# receiver.net
KiCad netlist of a schematic drawn in EAGLE
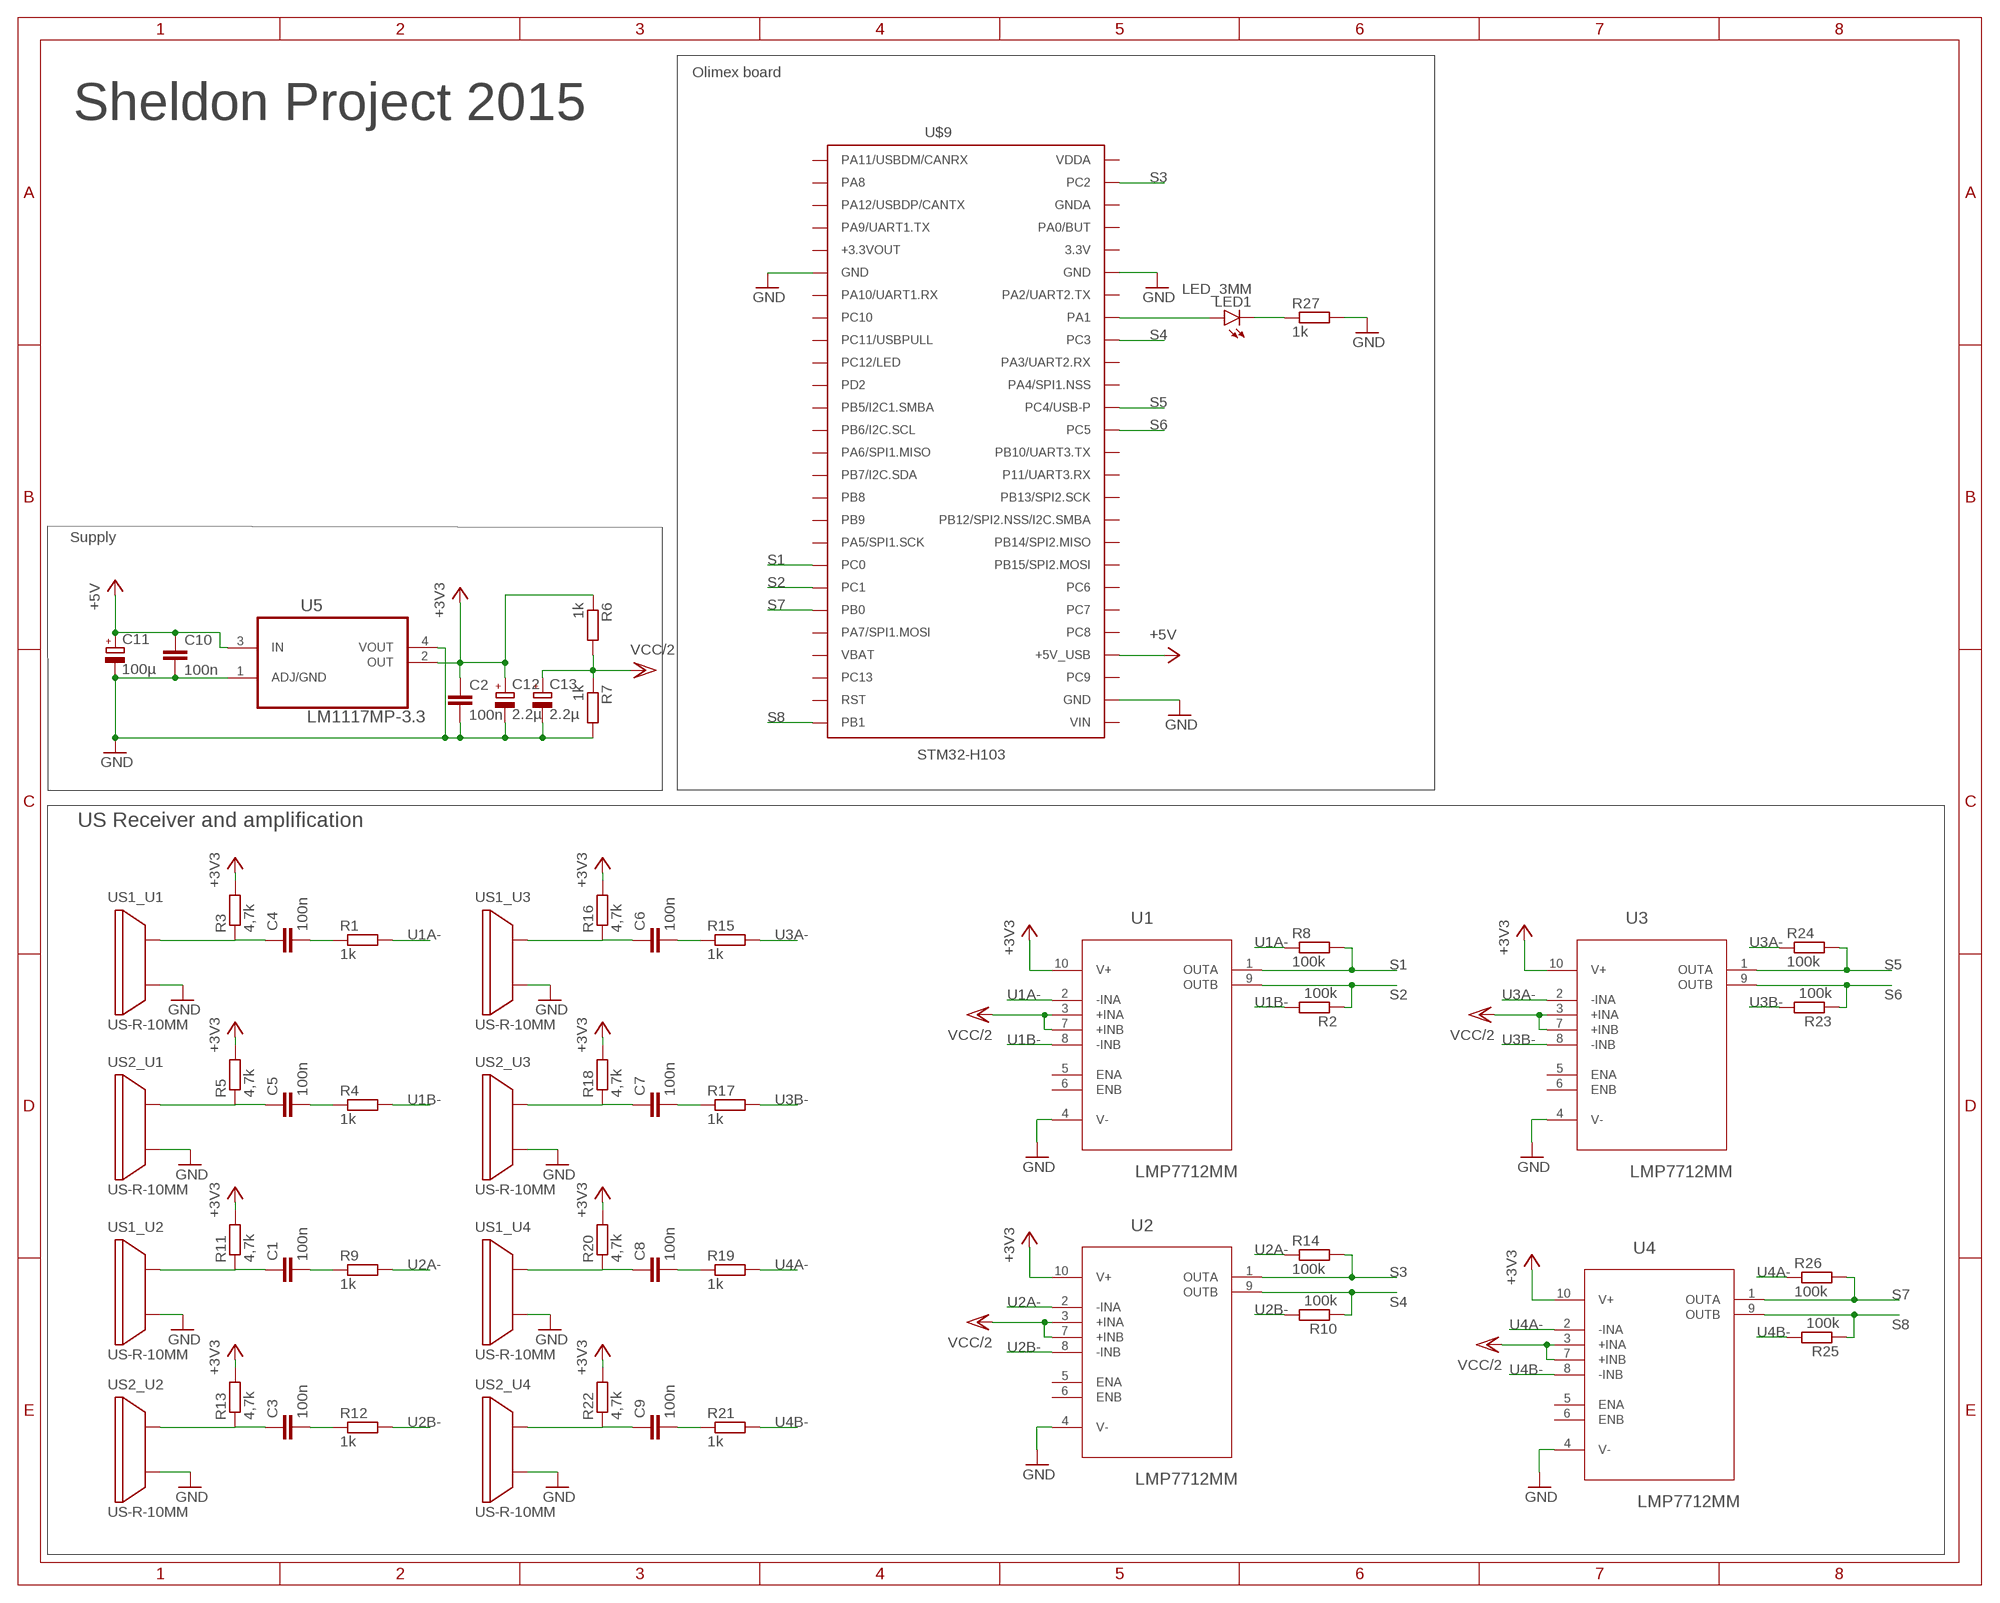
[diagram p0: schematic, sheet 1]

(export (version "E")
  (design (tool "Eeschema 10.0.6"))
  (components
    (comp (ref "C1")
      (value "100n")
      (footprint "eagle-import:C0603")
      (libsource (lib "eagle-import") (part "C-EUC0603"))
    )
    (comp (ref "C2")
      (value "100n")
      (footprint "eagle-import:C0603")
      (libsource (lib "eagle-import") (part "C-EUC0603"))
    )
    (comp (ref "C3")
      (value "100n")
      (footprint "eagle-import:C0603")
      (libsource (lib "eagle-import") (part "C-EUC0603"))
    )
    (comp (ref "C4")
      (value "100n")
      (footprint "eagle-import:C0603")
      (libsource (lib "eagle-import") (part "C-EUC0603"))
    )
    (comp (ref "C5")
      (value "100n")
      (footprint "eagle-import:C0603")
      (libsource (lib "eagle-import") (part "C-EUC0603"))
    )
    (comp (ref "C6")
      (value "100n")
      (footprint "eagle-import:C0603")
      (libsource (lib "eagle-import") (part "C-EUC0603"))
    )
    (comp (ref "C7")
      (value "100n")
      (footprint "eagle-import:C0603")
      (libsource (lib "eagle-import") (part "C-EUC0603"))
    )
    (comp (ref "C8")
      (value "100n")
      (footprint "eagle-import:C0603")
      (libsource (lib "eagle-import") (part "C-EUC0603"))
    )
    (comp (ref "C9")
      (value "100n")
      (footprint "eagle-import:C0603")
      (libsource (lib "eagle-import") (part "C-EUC0603"))
    )
    (comp (ref "C10")
      (value "100n")
      (footprint "eagle-import:C0603")
      (libsource (lib "eagle-import") (part "C-EUC0603"))
    )
    (comp (ref "C11")
      (value "100µ")
      (footprint "eagle-import:E2,5-6")
      (libsource (lib "eagle-import") (part "CPOL_DIAM5MM"))
    )
    (comp (ref "C12")
      (value "2.2µ")
      (footprint "eagle-import:E2,5-6")
      (libsource (lib "eagle-import") (part "CPOL_DIAM5MM"))
    )
    (comp (ref "C13")
      (value "2.2µ")
      (footprint "eagle-import:E2,5-6")
      (libsource (lib "eagle-import") (part "CPOL_DIAM5MM"))
    )
    (comp (ref "LED1")
      (value "LED_3MM")
      (footprint "eagle-import:LED3MM")
      (libsource (lib "eagle-import") (part "LED_3MM"))
    )
    (comp (ref "R1")
      (value "1k")
      (footprint "eagle-import:R0603")
      (libsource (lib "eagle-import") (part "R-EU_R0603"))
    )
    (comp (ref "R2")
      (value "100k")
      (footprint "eagle-import:R0603")
      (libsource (lib "eagle-import") (part "R-EU_R0603"))
    )
    (comp (ref "R3")
      (value "4,7k")
      (footprint "eagle-import:R0603")
      (libsource (lib "eagle-import") (part "R-EU_R0603"))
    )
    (comp (ref "R4")
      (value "1k")
      (footprint "eagle-import:R0603")
      (libsource (lib "eagle-import") (part "R-EU_R0603"))
    )
    (comp (ref "R5")
      (value "4,7k")
      (footprint "eagle-import:R0603")
      (libsource (lib "eagle-import") (part "R-EU_R0603"))
    )
    (comp (ref "R6")
      (value "1k")
      (footprint "eagle-import:R0603")
      (libsource (lib "eagle-import") (part "R-EU_R0603"))
    )
    (comp (ref "R7")
      (value "1k")
      (footprint "eagle-import:R0603")
      (libsource (lib "eagle-import") (part "R-EU_R0603"))
    )
    (comp (ref "R8")
      (value "100k")
      (footprint "eagle-import:R0603")
      (libsource (lib "eagle-import") (part "R-EU_R0603"))
    )
    (comp (ref "R9")
      (value "1k")
      (footprint "eagle-import:R0603")
      (libsource (lib "eagle-import") (part "R-EU_R0603"))
    )
    (comp (ref "R10")
      (value "100k")
      (footprint "eagle-import:R0603")
      (libsource (lib "eagle-import") (part "R-EU_R0603"))
    )
    (comp (ref "R11")
      (value "4,7k")
      (footprint "eagle-import:R0603")
      (libsource (lib "eagle-import") (part "R-EU_R0603"))
    )
    (comp (ref "R12")
      (value "1k")
      (footprint "eagle-import:R0603")
      (libsource (lib "eagle-import") (part "R-EU_R0603"))
    )
    (comp (ref "R13")
      (value "4,7k")
      (footprint "eagle-import:R0603")
      (libsource (lib "eagle-import") (part "R-EU_R0603"))
    )
    (comp (ref "R14")
      (value "100k")
      (footprint "eagle-import:R0603")
      (libsource (lib "eagle-import") (part "R-EU_R0603"))
    )
    (comp (ref "R15")
      (value "1k")
      (footprint "eagle-import:R0603")
      (libsource (lib "eagle-import") (part "R-EU_R0603"))
    )
    (comp (ref "R16")
      (value "4,7k")
      (footprint "eagle-import:R0603")
      (libsource (lib "eagle-import") (part "R-EU_R0603"))
    )
    (comp (ref "R17")
      (value "1k")
      (footprint "eagle-import:R0603")
      (libsource (lib "eagle-import") (part "R-EU_R0603"))
    )
    (comp (ref "R18")
      (value "4,7k")
      (footprint "eagle-import:R0603")
      (libsource (lib "eagle-import") (part "R-EU_R0603"))
    )
    (comp (ref "R19")
      (value "1k")
      (footprint "eagle-import:R0603")
      (libsource (lib "eagle-import") (part "R-EU_R0603"))
    )
    (comp (ref "R20")
      (value "4,7k")
      (footprint "eagle-import:R0603")
      (libsource (lib "eagle-import") (part "R-EU_R0603"))
    )
    (comp (ref "R21")
      (value "1k")
      (footprint "eagle-import:R0603")
      (libsource (lib "eagle-import") (part "R-EU_R0603"))
    )
    (comp (ref "R22")
      (value "4,7k")
      (footprint "eagle-import:R0603")
      (libsource (lib "eagle-import") (part "R-EU_R0603"))
    )
    (comp (ref "R23")
      (value "100k")
      (footprint "eagle-import:R0603")
      (libsource (lib "eagle-import") (part "R-EU_R0603"))
    )
    (comp (ref "R24")
      (value "100k")
      (footprint "eagle-import:R0603")
      (libsource (lib "eagle-import") (part "R-EU_R0603"))
    )
    (comp (ref "R25")
      (value "100k")
      (footprint "eagle-import:R0603")
      (libsource (lib "eagle-import") (part "R-EU_R0603"))
    )
    (comp (ref "R26")
      (value "100k")
      (footprint "eagle-import:R0603")
      (libsource (lib "eagle-import") (part "R-EU_R0603"))
    )
    (comp (ref "R27")
      (value "1k")
      (footprint "eagle-import:R0603")
      (libsource (lib "eagle-import") (part "R-EU_R0603"))
    )
    (comp (ref "U$9")
      (value "STM32-H103")
      (footprint "eagle-import:STM32-H103")
      (libsource (lib "eagle-import") (part "STM32-H103"))
    )
    (comp (ref "U1")
      (value "LMP7712MM")
      (footprint "eagle-import:SOP50P490X110-10N")
      (libsource (lib "eagle-import") (part "LMP7712MM"))
    )
    (comp (ref "U2")
      (value "LMP7712MM")
      (footprint "eagle-import:SOP50P490X110-10N")
      (libsource (lib "eagle-import") (part "LMP7712MM"))
    )
    (comp (ref "U3")
      (value "LMP7712MM")
      (footprint "eagle-import:SOP50P490X110-10N")
      (libsource (lib "eagle-import") (part "LMP7712MM"))
    )
    (comp (ref "U4")
      (value "LMP7712MM")
      (footprint "eagle-import:SOP50P490X110-10N")
      (libsource (lib "eagle-import") (part "LMP7712MM"))
    )
    (comp (ref "U5")
      (value "LM1117MP-3.3")
      (footprint "eagle-import:SOT230P696X180-4N")
      (libsource (lib "eagle-import") (part "LM1117MP-3.3"))
    )
    (comp (ref "US1_U1")
      (value "US-R-10MM")
      (footprint "eagle-import:US-R-10MM")
      (libsource (lib "eagle-import") (part "US-R-10MM"))
    )
    (comp (ref "US1_U2")
      (value "US-R-10MM")
      (footprint "eagle-import:US-R-10MM")
      (libsource (lib "eagle-import") (part "US-R-10MM"))
    )
    (comp (ref "US1_U3")
      (value "US-R-10MM")
      (footprint "eagle-import:US-R-10MM")
      (libsource (lib "eagle-import") (part "US-R-10MM"))
    )
    (comp (ref "US1_U4")
      (value "US-R-10MM")
      (footprint "eagle-import:US-R-10MM")
      (libsource (lib "eagle-import") (part "US-R-10MM"))
    )
    (comp (ref "US2_U1")
      (value "US-R-10MM")
      (footprint "eagle-import:US-R-10MM")
      (libsource (lib "eagle-import") (part "US-R-10MM"))
    )
    (comp (ref "US2_U2")
      (value "US-R-10MM")
      (footprint "eagle-import:US-R-10MM")
      (libsource (lib "eagle-import") (part "US-R-10MM"))
    )
    (comp (ref "US2_U3")
      (value "US-R-10MM")
      (footprint "eagle-import:US-R-10MM")
      (libsource (lib "eagle-import") (part "US-R-10MM"))
    )
    (comp (ref "US2_U4")
      (value "US-R-10MM")
      (footprint "eagle-import:US-R-10MM")
      (libsource (lib "eagle-import") (part "US-R-10MM"))
    )
  )
  (nets
    (net (code "1") (name "+3V3") (class "Default")
      (node (ref "C12") (pin "+") (pinfunction "P$1_+") (pintype "passive"))
      (node (ref "C2") (pin "1") (pinfunction "1_1") (pintype "passive"))
      (node (ref "R11") (pin "2") (pinfunction "2_2") (pintype "passive"))
      (node (ref "R13") (pin "2") (pinfunction "2_2") (pintype "passive"))
      (node (ref "R16") (pin "2") (pinfunction "2_2") (pintype "passive"))
      (node (ref "R18") (pin "2") (pinfunction "2_2") (pintype "passive"))
      (node (ref "R20") (pin "2") (pinfunction "2_2") (pintype "passive"))
      (node (ref "R22") (pin "2") (pinfunction "2_2") (pintype "passive"))
      (node (ref "R3") (pin "2") (pinfunction "2_2") (pintype "passive"))
      (node (ref "R5") (pin "2") (pinfunction "2_2") (pintype "passive"))
      (node (ref "R6") (pin "1") (pinfunction "1_1") (pintype "passive"))
      (node (ref "U1") (pin "10") (pinfunction "V+_10") (pintype "power_in"))
      (node (ref "U2") (pin "10") (pinfunction "V+_10") (pintype "power_in"))
      (node (ref "U3") (pin "10") (pinfunction "V+_10") (pintype "power_in"))
      (node (ref "U4") (pin "10") (pinfunction "V+_10") (pintype "power_in"))
      (node (ref "U5") (pin "2") (pinfunction "OUT_2") (pintype "output"))
    )
    (net (code "2") (name "+5V") (class "Default")
      (node (ref "C10") (pin "1") (pinfunction "1_1") (pintype "passive"))
      (node (ref "C11") (pin "+") (pinfunction "P$1_+") (pintype "passive"))
      (node (ref "U$9") (pin "+5V_USB") (pinfunction "+5V_USB_+5V_USB") (pintype "bidirectional"))
      (node (ref "U5") (pin "3") (pinfunction "IN_3") (pintype "input"))
    )
    (net (code "3") (name "/S1") (class "Default")
      (node (ref "R8") (pin "2") (pinfunction "2_2") (pintype "passive"))
      (node (ref "U$9") (pin "PC0") (pinfunction "PC0_PC0") (pintype "bidirectional"))
      (node (ref "U1") (pin "1") (pinfunction "OUTA_1") (pintype "output"))
    )
    (net (code "4") (name "/S2") (class "Default")
      (node (ref "R2") (pin "1") (pinfunction "1_1") (pintype "passive"))
      (node (ref "U$9") (pin "PC1") (pinfunction "PC1_PC1") (pintype "bidirectional"))
      (node (ref "U1") (pin "9") (pinfunction "OUTB_9") (pintype "output"))
    )
    (net (code "5") (name "/S3") (class "Default")
      (node (ref "R14") (pin "2") (pinfunction "2_2") (pintype "passive"))
      (node (ref "U$9") (pin "PC2") (pinfunction "PC2_PC2") (pintype "bidirectional"))
      (node (ref "U2") (pin "1") (pinfunction "OUTA_1") (pintype "output"))
    )
    (net (code "6") (name "/S4") (class "Default")
      (node (ref "R10") (pin "1") (pinfunction "1_1") (pintype "passive"))
      (node (ref "U$9") (pin "PC3") (pinfunction "PC3_PC3") (pintype "bidirectional"))
      (node (ref "U2") (pin "9") (pinfunction "OUTB_9") (pintype "output"))
    )
    (net (code "7") (name "/S5") (class "Default")
      (node (ref "R24") (pin "2") (pinfunction "2_2") (pintype "passive"))
      (node (ref "U$9") (pin "PC4/USB-P") (pinfunction "PC4/USB-P_PC4/USB-P") (pintype "bidirectional"))
      (node (ref "U3") (pin "1") (pinfunction "OUTA_1") (pintype "output"))
    )
    (net (code "8") (name "/S6") (class "Default")
      (node (ref "R23") (pin "1") (pinfunction "1_1") (pintype "passive"))
      (node (ref "U$9") (pin "PC5") (pinfunction "PC5_PC5") (pintype "bidirectional"))
      (node (ref "U3") (pin "9") (pinfunction "OUTB_9") (pintype "output"))
    )
    (net (code "9") (name "/S7") (class "Default")
      (node (ref "R26") (pin "2") (pinfunction "2_2") (pintype "passive"))
      (node (ref "U$9") (pin "PB0") (pinfunction "PB0_PB0") (pintype "bidirectional"))
      (node (ref "U4") (pin "1") (pinfunction "OUTA_1") (pintype "output"))
    )
    (net (code "10") (name "/S8") (class "Default")
      (node (ref "R25") (pin "1") (pinfunction "1_1") (pintype "passive"))
      (node (ref "U$9") (pin "PB1") (pinfunction "PB1_PB1") (pintype "bidirectional"))
      (node (ref "U4") (pin "9") (pinfunction "OUTB_9") (pintype "output"))
    )
    (net (code "11") (name "/U1A-") (class "Default")
      (node (ref "R1") (pin "2") (pinfunction "2_2") (pintype "passive"))
      (node (ref "R8") (pin "1") (pinfunction "1_1") (pintype "passive"))
      (node (ref "U1") (pin "2") (pinfunction "-INA_2") (pintype "input"))
    )
    (net (code "12") (name "/U1B-") (class "Default")
      (node (ref "R2") (pin "2") (pinfunction "2_2") (pintype "passive"))
      (node (ref "R4") (pin "2") (pinfunction "2_2") (pintype "passive"))
      (node (ref "U1") (pin "8") (pinfunction "-INB_8") (pintype "input"))
    )
    (net (code "13") (name "/U2A-") (class "Default")
      (node (ref "R14") (pin "1") (pinfunction "1_1") (pintype "passive"))
      (node (ref "R9") (pin "2") (pinfunction "2_2") (pintype "passive"))
      (node (ref "U2") (pin "2") (pinfunction "-INA_2") (pintype "input"))
    )
    (net (code "14") (name "/U2B-") (class "Default")
      (node (ref "R10") (pin "2") (pinfunction "2_2") (pintype "passive"))
      (node (ref "R12") (pin "2") (pinfunction "2_2") (pintype "passive"))
      (node (ref "U2") (pin "8") (pinfunction "-INB_8") (pintype "input"))
    )
    (net (code "15") (name "/U3A-") (class "Default")
      (node (ref "R15") (pin "2") (pinfunction "2_2") (pintype "passive"))
      (node (ref "R24") (pin "1") (pinfunction "1_1") (pintype "passive"))
      (node (ref "U3") (pin "2") (pinfunction "-INA_2") (pintype "input"))
    )
    (net (code "16") (name "/U3B-") (class "Default")
      (node (ref "R17") (pin "2") (pinfunction "2_2") (pintype "passive"))
      (node (ref "R23") (pin "2") (pinfunction "2_2") (pintype "passive"))
      (node (ref "U3") (pin "8") (pinfunction "-INB_8") (pintype "input"))
    )
    (net (code "17") (name "/U4A-") (class "Default")
      (node (ref "R19") (pin "2") (pinfunction "2_2") (pintype "passive"))
      (node (ref "R26") (pin "1") (pinfunction "1_1") (pintype "passive"))
      (node (ref "U4") (pin "2") (pinfunction "-INA_2") (pintype "input"))
    )
    (net (code "18") (name "/U4B-") (class "Default")
      (node (ref "R21") (pin "2") (pinfunction "2_2") (pintype "passive"))
      (node (ref "R25") (pin "2") (pinfunction "2_2") (pintype "passive"))
      (node (ref "U4") (pin "8") (pinfunction "-INB_8") (pintype "input"))
    )
    (net (code "19") (name "GND") (class "Default")
      (node (ref "C10") (pin "2") (pinfunction "2_2") (pintype "passive"))
      (node (ref "C11") (pin "-") (pinfunction "P$2_-") (pintype "passive"))
      (node (ref "C12") (pin "-") (pinfunction "P$2_-") (pintype "passive"))
      (node (ref "C13") (pin "-") (pinfunction "P$2_-") (pintype "passive"))
      (node (ref "C2") (pin "2") (pinfunction "2_2") (pintype "passive"))
      (node (ref "R27") (pin "2") (pinfunction "2_2") (pintype "passive"))
      (node (ref "R7") (pin "2") (pinfunction "2_2") (pintype "passive"))
      (node (ref "U$9") (pin "GND@1") (pinfunction "GND_GND@1") (pintype "bidirectional"))
      (node (ref "U$9") (pin "GND@2") (pinfunction "GND_GND@2") (pintype "bidirectional"))
      (node (ref "U$9") (pin "GND@3") (pinfunction "GND_GND@3") (pintype "bidirectional"))
      (node (ref "U1") (pin "4") (pinfunction "V-_4") (pintype "power_in"))
      (node (ref "U2") (pin "4") (pinfunction "V-_4") (pintype "power_in"))
      (node (ref "U3") (pin "4") (pinfunction "V-_4") (pintype "power_in"))
      (node (ref "U4") (pin "4") (pinfunction "V-_4") (pintype "power_in"))
      (node (ref "U5") (pin "1") (pinfunction "ADJ/GND_1") (pintype "passive"))
      (node (ref "U5") (pin "4") (pinfunction "VOUT_4") (pintype "output"))
      (node (ref "US1_U1") (pin "P$2") (pinfunction "P$2_P$2") (pintype "output"))
      (node (ref "US1_U2") (pin "P$2") (pinfunction "P$2_P$2") (pintype "output"))
      (node (ref "US1_U3") (pin "P$2") (pinfunction "P$2_P$2") (pintype "output"))
      (node (ref "US1_U4") (pin "P$2") (pinfunction "P$2_P$2") (pintype "output"))
      (node (ref "US2_U1") (pin "P$2") (pinfunction "P$2_P$2") (pintype "output"))
      (node (ref "US2_U2") (pin "P$2") (pinfunction "P$2_P$2") (pintype "output"))
      (node (ref "US2_U3") (pin "P$2") (pinfunction "P$2_P$2") (pintype "output"))
      (node (ref "US2_U4") (pin "P$2") (pinfunction "P$2_P$2") (pintype "output"))
    )
    (net (code "20") (name "Net-(C1-Pad1)") (class "Default")
      (node (ref "C1") (pin "1") (pinfunction "1_1") (pintype "passive"))
      (node (ref "R11") (pin "1") (pinfunction "1_1") (pintype "passive"))
      (node (ref "US1_U2") (pin "P$1") (pinfunction "P$1_P$1") (pintype "output"))
    )
    (net (code "21") (name "Net-(C1-Pad2)") (class "Default")
      (node (ref "C1") (pin "2") (pinfunction "2_2") (pintype "passive"))
      (node (ref "R9") (pin "1") (pinfunction "1_1") (pintype "passive"))
    )
    (net (code "22") (name "Net-(C3-Pad1)") (class "Default")
      (node (ref "C3") (pin "1") (pinfunction "1_1") (pintype "passive"))
      (node (ref "R13") (pin "1") (pinfunction "1_1") (pintype "passive"))
      (node (ref "US2_U2") (pin "P$1") (pinfunction "P$1_P$1") (pintype "output"))
    )
    (net (code "23") (name "Net-(C3-Pad2)") (class "Default")
      (node (ref "C3") (pin "2") (pinfunction "2_2") (pintype "passive"))
      (node (ref "R12") (pin "1") (pinfunction "1_1") (pintype "passive"))
    )
    (net (code "24") (name "Net-(C4-Pad1)") (class "Default")
      (node (ref "C4") (pin "1") (pinfunction "1_1") (pintype "passive"))
      (node (ref "R3") (pin "1") (pinfunction "1_1") (pintype "passive"))
      (node (ref "US1_U1") (pin "P$1") (pinfunction "P$1_P$1") (pintype "output"))
    )
    (net (code "25") (name "Net-(C4-Pad2)") (class "Default")
      (node (ref "C4") (pin "2") (pinfunction "2_2") (pintype "passive"))
      (node (ref "R1") (pin "1") (pinfunction "1_1") (pintype "passive"))
    )
    (net (code "26") (name "Net-(C5-Pad1)") (class "Default")
      (node (ref "C5") (pin "1") (pinfunction "1_1") (pintype "passive"))
      (node (ref "R5") (pin "1") (pinfunction "1_1") (pintype "passive"))
      (node (ref "US2_U1") (pin "P$1") (pinfunction "P$1_P$1") (pintype "output"))
    )
    (net (code "27") (name "Net-(C5-Pad2)") (class "Default")
      (node (ref "C5") (pin "2") (pinfunction "2_2") (pintype "passive"))
      (node (ref "R4") (pin "1") (pinfunction "1_1") (pintype "passive"))
    )
    (net (code "28") (name "Net-(C6-Pad1)") (class "Default")
      (node (ref "C6") (pin "1") (pinfunction "1_1") (pintype "passive"))
      (node (ref "R16") (pin "1") (pinfunction "1_1") (pintype "passive"))
      (node (ref "US1_U3") (pin "P$1") (pinfunction "P$1_P$1") (pintype "output"))
    )
    (net (code "29") (name "Net-(C6-Pad2)") (class "Default")
      (node (ref "C6") (pin "2") (pinfunction "2_2") (pintype "passive"))
      (node (ref "R15") (pin "1") (pinfunction "1_1") (pintype "passive"))
    )
    (net (code "30") (name "Net-(C7-Pad1)") (class "Default")
      (node (ref "C7") (pin "1") (pinfunction "1_1") (pintype "passive"))
      (node (ref "R18") (pin "1") (pinfunction "1_1") (pintype "passive"))
      (node (ref "US2_U3") (pin "P$1") (pinfunction "P$1_P$1") (pintype "output"))
    )
    (net (code "31") (name "Net-(C7-Pad2)") (class "Default")
      (node (ref "C7") (pin "2") (pinfunction "2_2") (pintype "passive"))
      (node (ref "R17") (pin "1") (pinfunction "1_1") (pintype "passive"))
    )
    (net (code "32") (name "Net-(C8-Pad1)") (class "Default")
      (node (ref "C8") (pin "1") (pinfunction "1_1") (pintype "passive"))
      (node (ref "R20") (pin "1") (pinfunction "1_1") (pintype "passive"))
      (node (ref "US1_U4") (pin "P$1") (pinfunction "P$1_P$1") (pintype "output"))
    )
    (net (code "33") (name "Net-(C8-Pad2)") (class "Default")
      (node (ref "C8") (pin "2") (pinfunction "2_2") (pintype "passive"))
      (node (ref "R19") (pin "1") (pinfunction "1_1") (pintype "passive"))
    )
    (net (code "34") (name "Net-(C9-Pad1)") (class "Default")
      (node (ref "C9") (pin "1") (pinfunction "1_1") (pintype "passive"))
      (node (ref "R22") (pin "1") (pinfunction "1_1") (pintype "passive"))
      (node (ref "US2_U4") (pin "P$1") (pinfunction "P$1_P$1") (pintype "output"))
    )
    (net (code "35") (name "Net-(C9-Pad2)") (class "Default")
      (node (ref "C9") (pin "2") (pinfunction "2_2") (pintype "passive"))
      (node (ref "R21") (pin "1") (pinfunction "1_1") (pintype "passive"))
    )
    (net (code "36") (name "Net-(LED1-C)") (class "Default")
      (node (ref "LED1") (pin "K") (pinfunction "C_K") (pintype "passive"))
      (node (ref "R27") (pin "1") (pinfunction "1_1") (pintype "passive"))
    )
    (net (code "37") (name "Net-(LED1-PadA)") (class "Default")
      (node (ref "LED1") (pin "A") (pinfunction "A_A") (pintype "passive"))
      (node (ref "U$9") (pin "PA1") (pinfunction "PA1_PA1") (pintype "bidirectional"))
    )
    (net (code "38") (name "VCC{slash}2") (class "Default")
      (node (ref "C13") (pin "+") (pinfunction "P$1_+") (pintype "passive"))
      (node (ref "R6") (pin "2") (pinfunction "2_2") (pintype "passive"))
      (node (ref "R7") (pin "1") (pinfunction "1_1") (pintype "passive"))
      (node (ref "U1") (pin "3") (pinfunction "+INA_3") (pintype "input"))
      (node (ref "U1") (pin "7") (pinfunction "+INB_7") (pintype "input"))
      (node (ref "U2") (pin "3") (pinfunction "+INA_3") (pintype "input"))
      (node (ref "U2") (pin "7") (pinfunction "+INB_7") (pintype "input"))
      (node (ref "U3") (pin "3") (pinfunction "+INA_3") (pintype "input"))
      (node (ref "U3") (pin "7") (pinfunction "+INB_7") (pintype "input"))
      (node (ref "U4") (pin "3") (pinfunction "+INA_3") (pintype "input"))
      (node (ref "U4") (pin "7") (pinfunction "+INB_7") (pintype "input"))
    )
    (net (code "39") (name "unconnected-(U$9-Pad+3.3VOUT)") (class "Default")
      (node (ref "U$9") (pin "+3.3VOUT") (pinfunction "+3.3VOUT_+3.3VOUT") (pintype "bidirectional"))
    )
    (net (code "40") (name "unconnected-(U$9-Pad3.3V)") (class "Default")
      (node (ref "U$9") (pin "3.3V") (pinfunction "3.3V_3.3V") (pintype "bidirectional"))
    )
    (net (code "41") (name "unconnected-(U$9-PadGNDA)") (class "Default")
      (node (ref "U$9") (pin "GNDA") (pinfunction "GNDA_GNDA") (pintype "bidirectional"))
    )
    (net (code "42") (name "unconnected-(U$9-PadP11{slash}UART3.RX)") (class "Default")
      (node (ref "U$9") (pin "P11/UART3.RX") (pinfunction "P11/UART3.RX_P11/UART3.RX") (pintype "bidirectional"))
    )
    (net (code "43") (name "unconnected-(U$9-PadPA0{slash}BUT)") (class "Default")
      (node (ref "U$9") (pin "PA0/BUT") (pinfunction "PA0/BUT_PA0/BUT") (pintype "bidirectional"))
    )
    (net (code "44") (name "unconnected-(U$9-PadPA2{slash}UART2.TX)") (class "Default")
      (node (ref "U$9") (pin "PA2/UART2.TX") (pinfunction "PA2/UART2.TX_PA2/UART2.TX") (pintype "bidirectional"))
    )
    (net (code "45") (name "unconnected-(U$9-PadPA3{slash}UART2.RX)") (class "Default")
      (node (ref "U$9") (pin "PA3/UART2.RX") (pinfunction "PA3/UART2.RX_PA3/UART2.RX") (pintype "bidirectional"))
    )
    (net (code "46") (name "unconnected-(U$9-PadPA4{slash}SPI1.NSS)") (class "Default")
      (node (ref "U$9") (pin "PA4/SPI1.NSS") (pinfunction "PA4/SPI1.NSS_PA4/SPI1.NSS") (pintype "bidirectional"))
    )
    (net (code "47") (name "unconnected-(U$9-PadPA5{slash}SPI1.SCK)") (class "Default")
      (node (ref "U$9") (pin "PA5/SPI1.SCK") (pinfunction "PA5/SPI1.SCK_PA5/SPI1.SCK") (pintype "bidirectional"))
    )
    (net (code "48") (name "unconnected-(U$9-PadPA6{slash}SPI1.MISO)") (class "Default")
      (node (ref "U$9") (pin "PA6/SPI1.MISO") (pinfunction "PA6/SPI1.MISO_PA6/SPI1.MISO") (pintype "bidirectional"))
    )
    (net (code "49") (name "unconnected-(U$9-PadPA7{slash}SPI1.MOSI)") (class "Default")
      (node (ref "U$9") (pin "PA7/SPI1.MOSI") (pinfunction "PA7/SPI1.MOSI_PA7/SPI1.MOSI") (pintype "bidirectional"))
    )
    (net (code "50") (name "unconnected-(U$9-PadPA8)") (class "Default")
      (node (ref "U$9") (pin "PA8") (pinfunction "PA8_PA8") (pintype "bidirectional"))
    )
    (net (code "51") (name "unconnected-(U$9-PadPA9{slash}UART1.TX)") (class "Default")
      (node (ref "U$9") (pin "PA9/UART1.TX") (pinfunction "PA9/UART1.TX_PA9/UART1.TX") (pintype "bidirectional"))
    )
    (net (code "52") (name "unconnected-(U$9-PadPA10{slash}UART1.RX)") (class "Default")
      (node (ref "U$9") (pin "PA10/UART1.RX") (pinfunction "PA10/UART1.RX_PA10/UART1.RX") (pintype "bidirectional"))
    )
    (net (code "53") (name "unconnected-(U$9-PadPA11{slash}USBDM{slash}CANRX)") (class "Default")
      (node (ref "U$9") (pin "PA11/USBDM/CANRX") (pinfunction "PA11/USBDM/CANRX_PA11/USBDM/CANRX") (pintype "bidirectional"))
    )
    (net (code "54") (name "unconnected-(U$9-PadPA12{slash}USBDP{slash}CANTX)") (class "Default")
      (node (ref "U$9") (pin "PA12/USBDP/CANTX") (pinfunction "PA12/USBDP/CANTX_PA12/USBDP/CANTX") (pintype "bidirectional"))
    )
    (net (code "55") (name "unconnected-(U$9-PadPB5{slash}I2C1.SMBA)") (class "Default")
      (node (ref "U$9") (pin "PB5/I2C1.SMBA") (pinfunction "PB5/I2C1.SMBA_PB5/I2C1.SMBA") (pintype "bidirectional"))
    )
    (net (code "56") (name "unconnected-(U$9-PadPB6{slash}I2C.SCL)") (class "Default")
      (node (ref "U$9") (pin "PB6/I2C.SCL") (pinfunction "PB6/I2C.SCL_PB6/I2C.SCL") (pintype "bidirectional"))
    )
    (net (code "57") (name "unconnected-(U$9-PadPB7{slash}I2C.SDA)") (class "Default")
      (node (ref "U$9") (pin "PB7/I2C.SDA") (pinfunction "PB7/I2C.SDA_PB7/I2C.SDA") (pintype "bidirectional"))
    )
    (net (code "58") (name "unconnected-(U$9-PadPB8)") (class "Default")
      (node (ref "U$9") (pin "PB8") (pinfunction "PB8_PB8") (pintype "bidirectional"))
    )
    (net (code "59") (name "unconnected-(U$9-PadPB9)") (class "Default")
      (node (ref "U$9") (pin "PB9") (pinfunction "PB9_PB9") (pintype "bidirectional"))
    )
    (net (code "60") (name "unconnected-(U$9-PadPB10{slash}UART3.TX)") (class "Default")
      (node (ref "U$9") (pin "PB10/UART3.TX") (pinfunction "PB10/UART3.TX_PB10/UART3.TX") (pintype "bidirectional"))
    )
    (net (code "61") (name "unconnected-(U$9-PadPB12{slash}SPI2.NSS{slash}I2C.SMBA)") (class "Default")
      (node (ref "U$9") (pin "PB12/SPI2.NSS/I2C.SMBA") (pinfunction "PB12/SPI2.NSS/I2C.SMBA_PB12/SPI2.NSS/I2C.SMBA") (pintype "bidirectional"))
    )
    (net (code "62") (name "unconnected-(U$9-PadPB13{slash}SPI2.SCK)") (class "Default")
      (node (ref "U$9") (pin "PB13/SPI2.SCK") (pinfunction "PB13/SPI2.SCK_PB13/SPI2.SCK") (pintype "bidirectional"))
    )
    (net (code "63") (name "unconnected-(U$9-PadPB14{slash}SPI2.MISO)") (class "Default")
      (node (ref "U$9") (pin "PB14/SPI2.MISO") (pinfunction "PB14/SPI2.MISO_PB14/SPI2.MISO") (pintype "bidirectional"))
    )
    (net (code "64") (name "unconnected-(U$9-PadPB15{slash}SPI2.MOSI)") (class "Default")
      (node (ref "U$9") (pin "PB15/SPI2.MOSI") (pinfunction "PB15/SPI2.MOSI_PB15/SPI2.MOSI") (pintype "bidirectional"))
    )
    (net (code "65") (name "unconnected-(U$9-PadPC6)") (class "Default")
      (node (ref "U$9") (pin "PC6") (pinfunction "PC6_PC6") (pintype "bidirectional"))
    )
    (net (code "66") (name "unconnected-(U$9-PadPC7)") (class "Default")
      (node (ref "U$9") (pin "PC7") (pinfunction "PC7_PC7") (pintype "bidirectional"))
    )
    (net (code "67") (name "unconnected-(U$9-PadPC8)") (class "Default")
      (node (ref "U$9") (pin "PC8") (pinfunction "PC8_PC8") (pintype "bidirectional"))
    )
    (net (code "68") (name "unconnected-(U$9-PadPC9)") (class "Default")
      (node (ref "U$9") (pin "PC9") (pinfunction "PC9_PC9") (pintype "bidirectional"))
    )
    (net (code "69") (name "unconnected-(U$9-PadPC10)") (class "Default")
      (node (ref "U$9") (pin "PC10") (pinfunction "PC10_PC10") (pintype "bidirectional"))
    )
    (net (code "70") (name "unconnected-(U$9-PadPC11{slash}USBPULL)") (class "Default")
      (node (ref "U$9") (pin "PC11/USBPULL") (pinfunction "PC11/USBPULL_PC11/USBPULL") (pintype "bidirectional"))
    )
    (net (code "71") (name "unconnected-(U$9-PadPC12{slash}LED)") (class "Default")
      (node (ref "U$9") (pin "PC12/LED") (pinfunction "PC12/LED_PC12/LED") (pintype "bidirectional"))
    )
    (net (code "72") (name "unconnected-(U$9-PadPC13)") (class "Default")
      (node (ref "U$9") (pin "PC13") (pinfunction "PC13_PC13") (pintype "bidirectional"))
    )
    (net (code "73") (name "unconnected-(U$9-PadPD2)") (class "Default")
      (node (ref "U$9") (pin "PD2") (pinfunction "PD2_PD2") (pintype "bidirectional"))
    )
    (net (code "74") (name "unconnected-(U$9-PadRST)") (class "Default")
      (node (ref "U$9") (pin "RST") (pinfunction "RST_RST") (pintype "bidirectional"))
    )
    (net (code "75") (name "unconnected-(U$9-PadVBAT)") (class "Default")
      (node (ref "U$9") (pin "VBAT") (pinfunction "VBAT_VBAT") (pintype "bidirectional"))
    )
    (net (code "76") (name "unconnected-(U$9-PadVDDA)") (class "Default")
      (node (ref "U$9") (pin "VDDA") (pinfunction "VDDA_VDDA") (pintype "bidirectional"))
    )
    (net (code "77") (name "unconnected-(U$9-PadVIN)") (class "Default")
      (node (ref "U$9") (pin "VIN") (pinfunction "VIN_VIN") (pintype "bidirectional"))
    )
    (net (code "78") (name "unconnected-(U1-ENA-Pad5)") (class "Default")
      (node (ref "U1") (pin "5") (pinfunction "ENA_5") (pintype "input"))
    )
    (net (code "79") (name "unconnected-(U1-ENB-Pad6)") (class "Default")
      (node (ref "U1") (pin "6") (pinfunction "ENB_6") (pintype "input"))
    )
    (net (code "80") (name "unconnected-(U2-ENA-Pad5)") (class "Default")
      (node (ref "U2") (pin "5") (pinfunction "ENA_5") (pintype "input"))
    )
    (net (code "81") (name "unconnected-(U2-ENB-Pad6)") (class "Default")
      (node (ref "U2") (pin "6") (pinfunction "ENB_6") (pintype "input"))
    )
    (net (code "82") (name "unconnected-(U3-ENA-Pad5)") (class "Default")
      (node (ref "U3") (pin "5") (pinfunction "ENA_5") (pintype "input"))
    )
    (net (code "83") (name "unconnected-(U3-ENB-Pad6)") (class "Default")
      (node (ref "U3") (pin "6") (pinfunction "ENB_6") (pintype "input"))
    )
    (net (code "84") (name "unconnected-(U4-ENA-Pad5)") (class "Default")
      (node (ref "U4") (pin "5") (pinfunction "ENA_5") (pintype "input"))
    )
    (net (code "85") (name "unconnected-(U4-ENB-Pad6)") (class "Default")
      (node (ref "U4") (pin "6") (pinfunction "ENB_6") (pintype "input"))
    )
  )
)
